# PCB-IO-PROTECTION-2.net
KiCad netlist of a schematic drawn in Altium Designer
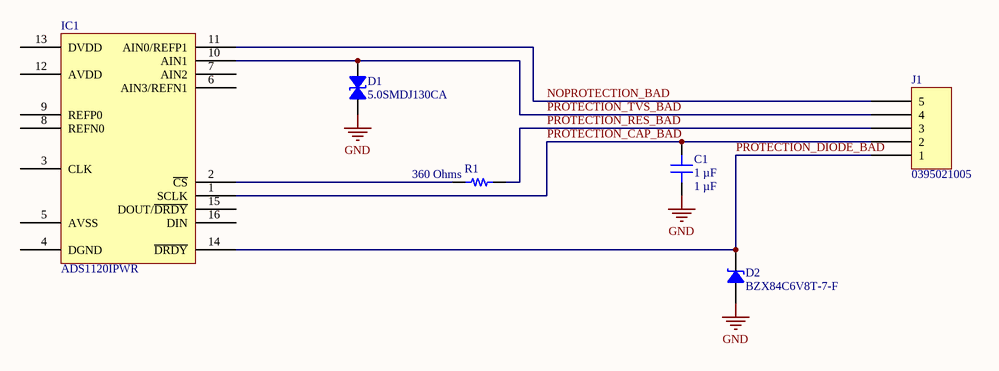
[diagram p0: PCB-IO-PROTECTION-2.SchDoc]

(export (version "E")
  (design (tool "Eeschema 10.0.6"))
  (components
    (comp (ref "C1")
      (value "1 µF")
      (footprint "CAP 0603_1608")
      (description "CAP CER 1UF 16V X7R 0603")
      (fields (field (name "PART NUMBER") "C0603C105K4RACAUTO") (field (name "ALTIUM_VALUE") "1 µF"))
      (libsource (lib "Celestial Altium Library - altium_library") (part "Capacitor"))
    )
    (comp (ref "D1")
      (value "5.0SMDJ130CA")
      (footprint "DO214AB SMC")
      (description "TVS DIODE 130VWM 209VC DO214AB")
      (libsource (lib "Celestial Altium Library - altium_library") (part "Diode TVS"))
    )
    (comp (ref "D2")
      (value "BZX84C6V8T-7-F")
      (footprint "DIODES SOT-523")
      (description "DIODE ZENER 6.8V 150MW SOT523")
      (libsource (lib "Celestial Altium Library - altium_library") (part "Diode Zener"))
    )
    (comp (ref "IC1")
      (value "ADS1120IPWR")
      (footprint "TI TSSOP-16 PW")
      (description "IC ADC 16BIT SIGMA-DELTA 16TSSOP")
      (libsource (lib "Celestial Altium Library - altium_library") (part "TI ADS1120 TSSOP"))
    )
    (comp (ref "J1")
      (value "0395021005")
      (footprint "MOLEX 395021005")
      (description "TERM BLOCK HDR 5POS 90DEG 3.5MM")
      (libsource (lib "Celestial Altium Library - altium_library") (part "5 Pin"))
    )
    (comp (ref "R1")
      (value "360 Ohms")
      (footprint "RES 0603_1608")
      (description "RES SMD 360 OHM 0.1% 1/5W 0603")
      (fields (field (name "PART NUMBER") "ERJ-PB3B3600V"))
      (libsource (lib "Celestial Altium Library - altium_library") (part "Resistor"))
    )
  )
  (nets
    (net (code "1") (name "/NOPROTECTION_BAD") (class "Default")
      (node (ref "IC1") (pin "11") (pinfunction "AIN0/REFP1_11") (pintype "passive"))
      (node (ref "J1") (pin "5") (pinfunction "5_5") (pintype "passive"))
    )
    (net (code "2") (name "/PROTECTION_CAP_BAD") (class "Default")
      (node (ref "C1") (pin "2") (pinfunction "2_2") (pintype "passive"))
      (node (ref "IC1") (pin "1") (pinfunction "SCLK_1") (pintype "passive"))
      (node (ref "J1") (pin "2") (pinfunction "2_2") (pintype "passive"))
    )
    (net (code "3") (name "/PROTECTION_DIODE_BAD") (class "Default")
      (node (ref "D2") (pin "2") (pinfunction "2_2") (pintype "passive"))
      (node (ref "IC1") (pin "14") (pinfunction "~{DRDY}_14") (pintype "passive"))
      (node (ref "J1") (pin "1") (pinfunction "1_1") (pintype "passive"))
    )
    (net (code "4") (name "/PROTECTION_RES_BAD") (class "Default")
      (node (ref "J1") (pin "3") (pinfunction "3_3") (pintype "passive"))
      (node (ref "R1") (pin "2") (pinfunction "2_2") (pintype "passive"))
    )
    (net (code "5") (name "/PROTECTION_TVS_BAD") (class "Default")
      (node (ref "D1") (pin "2") (pinfunction "2_2") (pintype "passive"))
      (node (ref "IC1") (pin "10") (pinfunction "AIN1_10") (pintype "passive"))
      (node (ref "J1") (pin "4") (pinfunction "4_4") (pintype "passive"))
    )
    (net (code "6") (name "GND") (class "Default")
      (node (ref "C1") (pin "1") (pinfunction "1_1") (pintype "passive"))
      (node (ref "D1") (pin "1") (pinfunction "1_1") (pintype "passive"))
      (node (ref "D2") (pin "1") (pinfunction "1_1") (pintype "passive"))
    )
    (net (code "7") (name "Net-(IC1-~{CS})") (class "Default")
      (node (ref "IC1") (pin "2") (pinfunction "~{CS}_2") (pintype "passive"))
      (node (ref "R1") (pin "1") (pinfunction "1_1") (pintype "passive"))
    )
    (net (code "8") (name "unconnected-(IC1-AIN2-Pad7)") (class "Default")
      (node (ref "IC1") (pin "7") (pinfunction "AIN2_7") (pintype "passive"))
    )
    (net (code "9") (name "unconnected-(IC1-AIN3{slash}REFN1-Pad6)") (class "Default")
      (node (ref "IC1") (pin "6") (pinfunction "AIN3/REFN1_6") (pintype "passive"))
    )
    (net (code "10") (name "unconnected-(IC1-AVDD-Pad12)") (class "Default")
      (node (ref "IC1") (pin "12") (pinfunction "AVDD_12") (pintype "passive"))
    )
    (net (code "11") (name "unconnected-(IC1-AVSS-Pad5)") (class "Default")
      (node (ref "IC1") (pin "5") (pinfunction "AVSS_5") (pintype "passive"))
    )
    (net (code "12") (name "unconnected-(IC1-CLK-Pad3)") (class "Default")
      (node (ref "IC1") (pin "3") (pinfunction "CLK_3") (pintype "passive"))
    )
    (net (code "13") (name "unconnected-(IC1-DGND-Pad4)") (class "Default")
      (node (ref "IC1") (pin "4") (pinfunction "DGND_4") (pintype "passive"))
    )
    (net (code "14") (name "unconnected-(IC1-DIN-Pad16)") (class "Default")
      (node (ref "IC1") (pin "16") (pinfunction "DIN_16") (pintype "passive"))
    )
    (net (code "15") (name "unconnected-(IC1-DOUT{slash}~{DRDY}-Pad15)") (class "Default")
      (node (ref "IC1") (pin "15") (pinfunction "DOUT/~{DRDY}_15") (pintype "passive"))
    )
    (net (code "16") (name "unconnected-(IC1-DVDD-Pad13)") (class "Default")
      (node (ref "IC1") (pin "13") (pinfunction "DVDD_13") (pintype "passive"))
    )
    (net (code "17") (name "unconnected-(IC1-REFN0-Pad8)") (class "Default")
      (node (ref "IC1") (pin "8") (pinfunction "REFN0_8") (pintype "passive"))
    )
    (net (code "18") (name "unconnected-(IC1-REFP0-Pad9)") (class "Default")
      (node (ref "IC1") (pin "9") (pinfunction "REFP0_9") (pintype "passive"))
    )
  )
)
